# industrialSensorModule.net
KiCad netlist of a schematic drawn in EAGLE
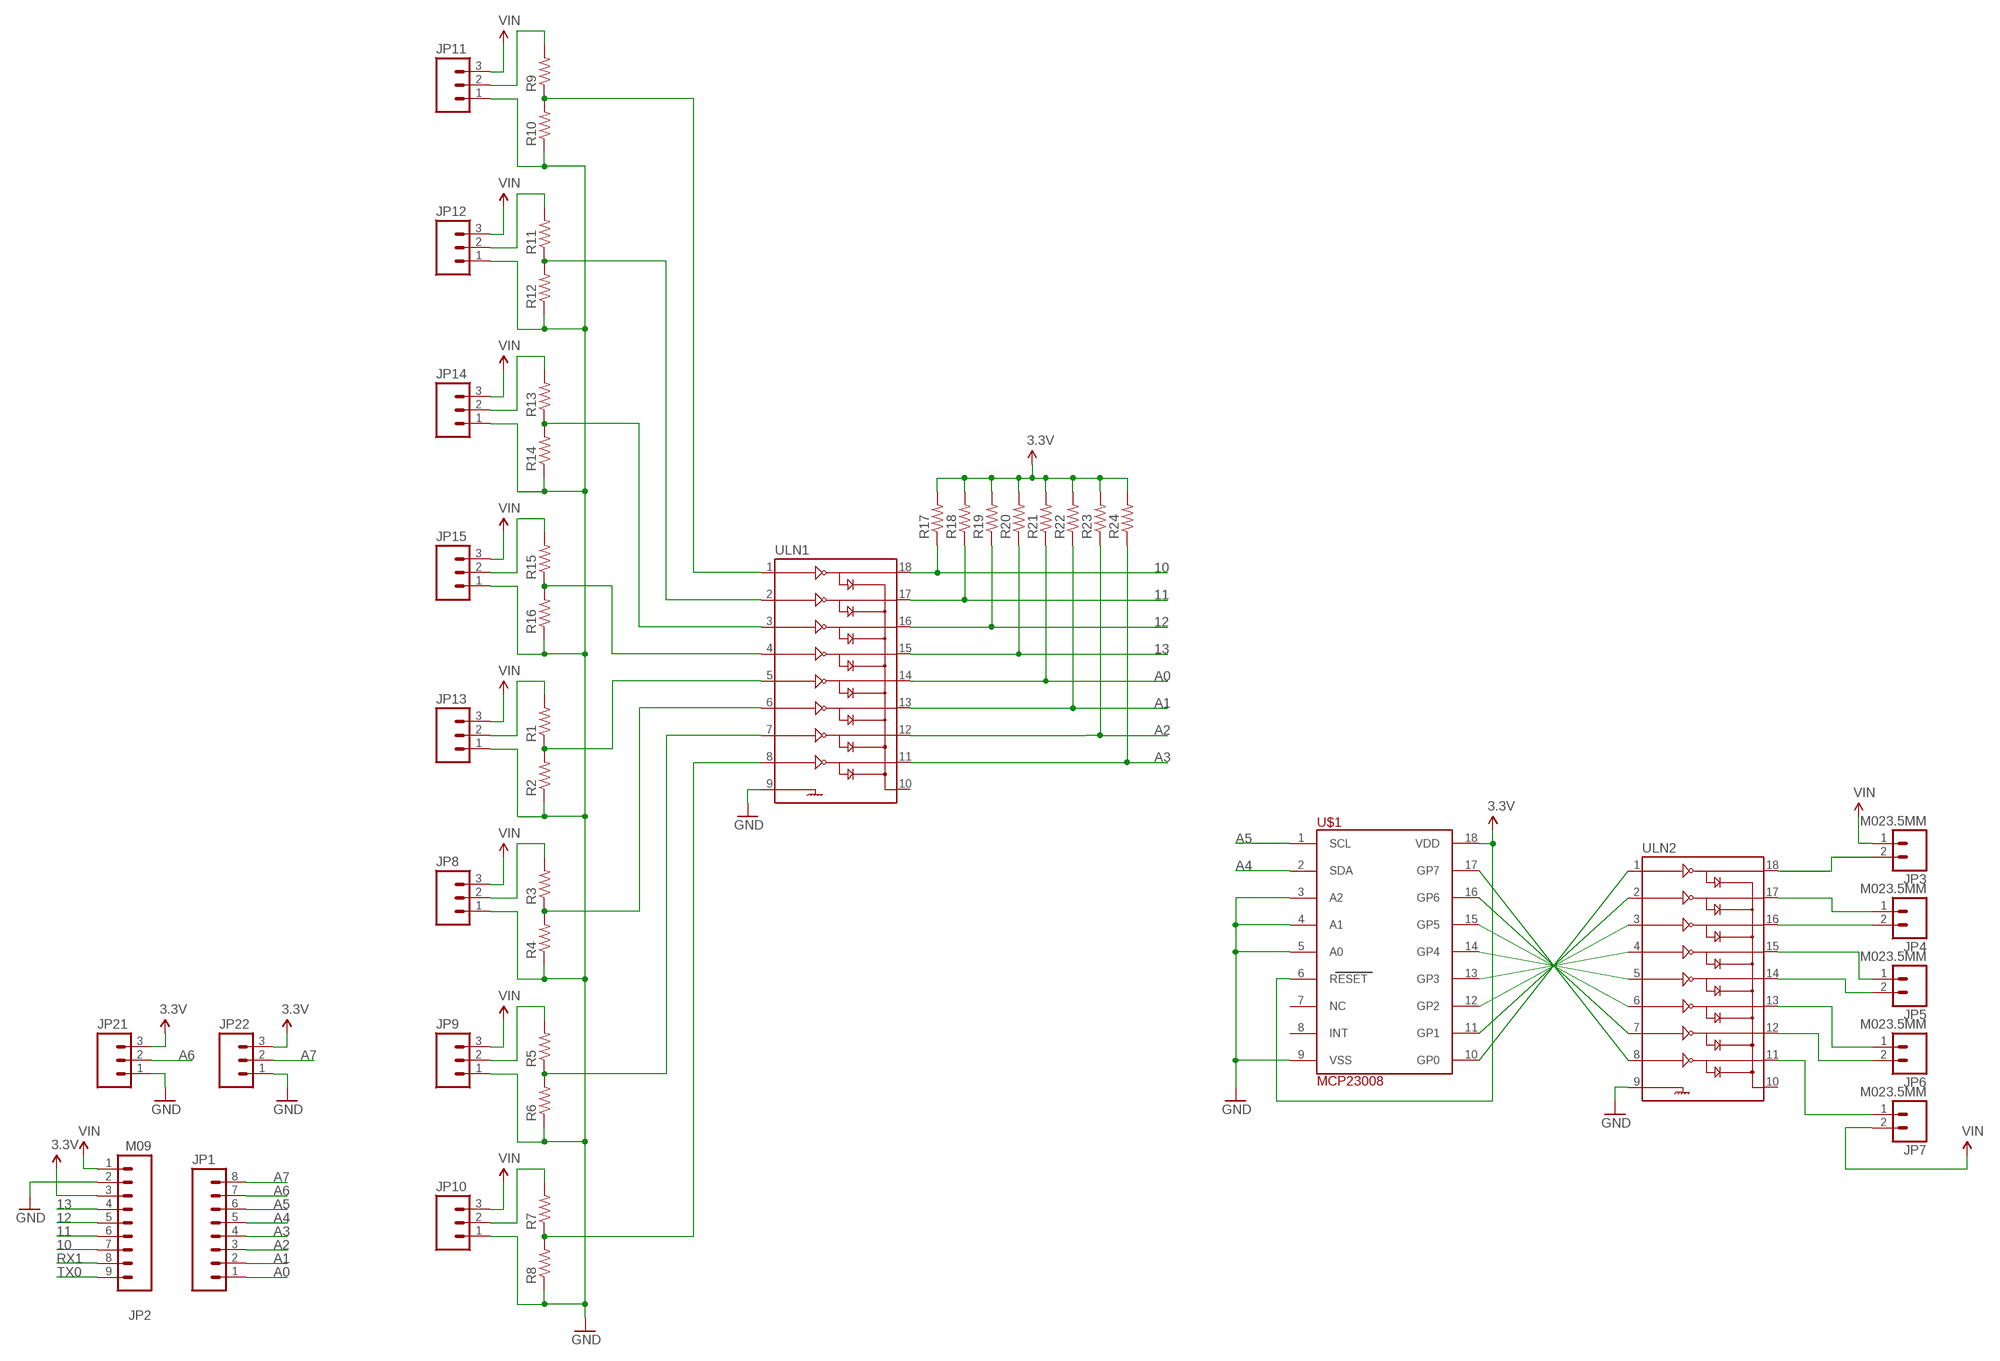
[diagram p0: schematic, sheet 1]

(export (version "E")
  (design (tool "Eeschema 10.0.6"))
  (components
    (comp (ref "JP1")
      (value "M081X08")
      (footprint "eagle-import:1X08")
      (libsource (lib "eagle-import") (part "M081X08"))
    )
    (comp (ref "JP2")
      (value "M09")
      (footprint "eagle-import:1X09")
      (libsource (lib "eagle-import") (part "M09"))
    )
    (comp (ref "JP3")
      (value "M023.5MM")
      (footprint "eagle-import:SCREWTERMINAL-3.5MM-2")
      (libsource (lib "eagle-import") (part "M023.5MM"))
    )
    (comp (ref "JP4")
      (value "M023.5MM")
      (footprint "eagle-import:SCREWTERMINAL-3.5MM-2")
      (libsource (lib "eagle-import") (part "M023.5MM"))
    )
    (comp (ref "JP5")
      (value "M023.5MM")
      (footprint "eagle-import:SCREWTERMINAL-3.5MM-2")
      (libsource (lib "eagle-import") (part "M023.5MM"))
    )
    (comp (ref "JP6")
      (value "M023.5MM")
      (footprint "eagle-import:SCREWTERMINAL-3.5MM-2")
      (libsource (lib "eagle-import") (part "M023.5MM"))
    )
    (comp (ref "JP7")
      (value "M023.5MM")
      (footprint "eagle-import:SCREWTERMINAL-3.5MM-2")
      (libsource (lib "eagle-import") (part "M023.5MM"))
    )
    (comp (ref "JP8")
      (value "M03SCREW")
      (footprint "eagle-import:SCREWTERMINAL-3.5MM-3")
      (libsource (lib "eagle-import") (part "M03SCREW"))
    )
    (comp (ref "JP9")
      (value "M03SCREW")
      (footprint "eagle-import:SCREWTERMINAL-3.5MM-3")
      (libsource (lib "eagle-import") (part "M03SCREW"))
    )
    (comp (ref "JP10")
      (value "M03SCREW")
      (footprint "eagle-import:SCREWTERMINAL-3.5MM-3")
      (libsource (lib "eagle-import") (part "M03SCREW"))
    )
    (comp (ref "JP11")
      (value "M03SCREW")
      (footprint "eagle-import:SCREWTERMINAL-3.5MM-3")
      (libsource (lib "eagle-import") (part "M03SCREW"))
    )
    (comp (ref "JP12")
      (value "M03SCREW")
      (footprint "eagle-import:SCREWTERMINAL-3.5MM-3")
      (libsource (lib "eagle-import") (part "M03SCREW"))
    )
    (comp (ref "JP13")
      (value "M03SCREW")
      (footprint "eagle-import:SCREWTERMINAL-3.5MM-3")
      (libsource (lib "eagle-import") (part "M03SCREW"))
    )
    (comp (ref "JP14")
      (value "M03SCREW")
      (footprint "eagle-import:SCREWTERMINAL-3.5MM-3")
      (libsource (lib "eagle-import") (part "M03SCREW"))
    )
    (comp (ref "JP15")
      (value "M03SCREW")
      (footprint "eagle-import:SCREWTERMINAL-3.5MM-3")
      (libsource (lib "eagle-import") (part "M03SCREW"))
    )
    (comp (ref "JP21")
      (value "M03SCREW")
      (footprint "eagle-import:SCREWTERMINAL-3.5MM-3")
      (libsource (lib "eagle-import") (part "M03SCREW"))
    )
    (comp (ref "JP22")
      (value "M03SCREW")
      (footprint "eagle-import:SCREWTERMINAL-3.5MM-3")
      (libsource (lib "eagle-import") (part "M03SCREW"))
    )
    (comp (ref "R1")
      (value "RESISTOR1206")
      (footprint "eagle-import:1206")
      (libsource (lib "eagle-import") (part "RESISTOR1206"))
    )
    (comp (ref "R2")
      (value "RESISTOR1206")
      (footprint "eagle-import:1206")
      (libsource (lib "eagle-import") (part "RESISTOR1206"))
    )
    (comp (ref "R3")
      (value "RESISTOR1206")
      (footprint "eagle-import:1206")
      (libsource (lib "eagle-import") (part "RESISTOR1206"))
    )
    (comp (ref "R4")
      (value "RESISTOR1206")
      (footprint "eagle-import:1206")
      (libsource (lib "eagle-import") (part "RESISTOR1206"))
    )
    (comp (ref "R5")
      (value "RESISTOR1206")
      (footprint "eagle-import:1206")
      (libsource (lib "eagle-import") (part "RESISTOR1206"))
    )
    (comp (ref "R6")
      (value "RESISTOR1206")
      (footprint "eagle-import:1206")
      (libsource (lib "eagle-import") (part "RESISTOR1206"))
    )
    (comp (ref "R7")
      (value "RESISTOR1206")
      (footprint "eagle-import:1206")
      (libsource (lib "eagle-import") (part "RESISTOR1206"))
    )
    (comp (ref "R8")
      (value "RESISTOR1206")
      (footprint "eagle-import:1206")
      (libsource (lib "eagle-import") (part "RESISTOR1206"))
    )
    (comp (ref "R9")
      (value "RESISTOR1206")
      (footprint "eagle-import:1206")
      (libsource (lib "eagle-import") (part "RESISTOR1206"))
    )
    (comp (ref "R10")
      (value "RESISTOR1206")
      (footprint "eagle-import:1206")
      (libsource (lib "eagle-import") (part "RESISTOR1206"))
    )
    (comp (ref "R11")
      (value "RESISTOR1206")
      (footprint "eagle-import:1206")
      (libsource (lib "eagle-import") (part "RESISTOR1206"))
    )
    (comp (ref "R12")
      (value "RESISTOR1206")
      (footprint "eagle-import:1206")
      (libsource (lib "eagle-import") (part "RESISTOR1206"))
    )
    (comp (ref "R13")
      (value "RESISTOR1206")
      (footprint "eagle-import:1206")
      (libsource (lib "eagle-import") (part "RESISTOR1206"))
    )
    (comp (ref "R14")
      (value "RESISTOR1206")
      (footprint "eagle-import:1206")
      (libsource (lib "eagle-import") (part "RESISTOR1206"))
    )
    (comp (ref "R15")
      (value "RESISTOR1206")
      (footprint "eagle-import:1206")
      (libsource (lib "eagle-import") (part "RESISTOR1206"))
    )
    (comp (ref "R16")
      (value "RESISTOR1206")
      (footprint "eagle-import:1206")
      (libsource (lib "eagle-import") (part "RESISTOR1206"))
    )
    (comp (ref "R17")
      (value "RESISTOR1206")
      (footprint "eagle-import:1206")
      (libsource (lib "eagle-import") (part "RESISTOR1206"))
    )
    (comp (ref "R18")
      (value "RESISTOR1206")
      (footprint "eagle-import:1206")
      (libsource (lib "eagle-import") (part "RESISTOR1206"))
    )
    (comp (ref "R19")
      (value "RESISTOR1206")
      (footprint "eagle-import:1206")
      (libsource (lib "eagle-import") (part "RESISTOR1206"))
    )
    (comp (ref "R20")
      (value "RESISTOR1206")
      (footprint "eagle-import:1206")
      (libsource (lib "eagle-import") (part "RESISTOR1206"))
    )
    (comp (ref "R21")
      (value "RESISTOR1206")
      (footprint "eagle-import:1206")
      (libsource (lib "eagle-import") (part "RESISTOR1206"))
    )
    (comp (ref "R22")
      (value "RESISTOR1206")
      (footprint "eagle-import:1206")
      (libsource (lib "eagle-import") (part "RESISTOR1206"))
    )
    (comp (ref "R23")
      (value "RESISTOR1206")
      (footprint "eagle-import:1206")
      (libsource (lib "eagle-import") (part "RESISTOR1206"))
    )
    (comp (ref "R24")
      (value "RESISTOR1206")
      (footprint "eagle-import:1206")
      (libsource (lib "eagle-import") (part "RESISTOR1206"))
    )
    (comp (ref "U$1")
      (value "MCP23008")
      (footprint "eagle-import:SOICW-18")
      (libsource (lib "eagle-import") (part "MCP23008"))
    )
    (comp (ref "ULN1")
      (value "ULN2803SOICW")
      (footprint "eagle-import:SO18L")
      (libsource (lib "eagle-import") (part "ULN2803SOICW"))
    )
    (comp (ref "ULN2")
      (value "ULN2803SOICW")
      (footprint "eagle-import:SO18L")
      (libsource (lib "eagle-import") (part "ULN2803SOICW"))
    )
  )
  (nets
    (net (code "1") (name "/10") (class "Default")
      (node (ref "JP2") (pin "7") (pinfunction "7_7") (pintype "passive"))
      (node (ref "R17") (pin "1") (pinfunction "1_1") (pintype "passive"))
      (node (ref "ULN1") (pin "18") (pinfunction "18_18") (pintype "bidirectional"))
    )
    (net (code "2") (name "/11") (class "Default")
      (node (ref "JP2") (pin "6") (pinfunction "6_6") (pintype "passive"))
      (node (ref "R18") (pin "1") (pinfunction "1_1") (pintype "passive"))
      (node (ref "ULN1") (pin "17") (pinfunction "17_17") (pintype "bidirectional"))
    )
    (net (code "3") (name "/12") (class "Default")
      (node (ref "JP2") (pin "5") (pinfunction "5_5") (pintype "passive"))
      (node (ref "R19") (pin "1") (pinfunction "1_1") (pintype "passive"))
      (node (ref "ULN1") (pin "16") (pinfunction "16_16") (pintype "bidirectional"))
    )
    (net (code "4") (name "/13") (class "Default")
      (node (ref "JP2") (pin "4") (pinfunction "4_4") (pintype "passive"))
      (node (ref "R20") (pin "1") (pinfunction "1_1") (pintype "passive"))
      (node (ref "ULN1") (pin "15") (pinfunction "15_15") (pintype "bidirectional"))
    )
    (net (code "5") (name "/A0") (class "Default")
      (node (ref "JP1") (pin "1") (pinfunction "1_1") (pintype "passive"))
      (node (ref "R21") (pin "1") (pinfunction "1_1") (pintype "passive"))
      (node (ref "ULN1") (pin "14") (pinfunction "14_14") (pintype "bidirectional"))
    )
    (net (code "6") (name "/A1") (class "Default")
      (node (ref "JP1") (pin "2") (pinfunction "2_2") (pintype "passive"))
      (node (ref "R22") (pin "1") (pinfunction "1_1") (pintype "passive"))
      (node (ref "ULN1") (pin "13") (pinfunction "13_13") (pintype "bidirectional"))
    )
    (net (code "7") (name "/A2") (class "Default")
      (node (ref "JP1") (pin "3") (pinfunction "3_3") (pintype "passive"))
      (node (ref "R23") (pin "1") (pinfunction "1_1") (pintype "passive"))
      (node (ref "ULN1") (pin "12") (pinfunction "12_12") (pintype "bidirectional"))
    )
    (net (code "8") (name "/A3") (class "Default")
      (node (ref "JP1") (pin "4") (pinfunction "4_4") (pintype "passive"))
      (node (ref "R24") (pin "1") (pinfunction "1_1") (pintype "passive"))
      (node (ref "ULN1") (pin "11") (pinfunction "11_11") (pintype "bidirectional"))
    )
    (net (code "9") (name "/A4") (class "Default")
      (node (ref "JP1") (pin "5") (pinfunction "5_5") (pintype "passive"))
      (node (ref "U$1") (pin "2") (pinfunction "SDA_2") (pintype "bidirectional"))
    )
    (net (code "10") (name "/A5") (class "Default")
      (node (ref "JP1") (pin "6") (pinfunction "6_6") (pintype "passive"))
      (node (ref "U$1") (pin "1") (pinfunction "SCL_1") (pintype "bidirectional"))
    )
    (net (code "11") (name "/A6") (class "Default")
      (node (ref "JP1") (pin "7") (pinfunction "7_7") (pintype "passive"))
      (node (ref "JP21") (pin "2") (pinfunction "2_2") (pintype "passive"))
    )
    (net (code "12") (name "/A7") (class "Default")
      (node (ref "JP1") (pin "8") (pinfunction "8_8") (pintype "passive"))
      (node (ref "JP22") (pin "2") (pinfunction "2_2") (pintype "passive"))
    )
    (net (code "13") (name "/RX1") (class "Default")
      (node (ref "JP2") (pin "8") (pinfunction "8_8") (pintype "passive"))
    )
    (net (code "14") (name "/TX0") (class "Default")
      (node (ref "JP2") (pin "9") (pinfunction "9_9") (pintype "passive"))
    )
    (net (code "15") (name "3.3V") (class "Default")
      (node (ref "JP2") (pin "3") (pinfunction "3_3") (pintype "passive"))
      (node (ref "JP21") (pin "3") (pinfunction "3_3") (pintype "passive"))
      (node (ref "JP22") (pin "3") (pinfunction "3_3") (pintype "passive"))
      (node (ref "R17") (pin "2") (pinfunction "2_2") (pintype "passive"))
      (node (ref "R18") (pin "2") (pinfunction "2_2") (pintype "passive"))
      (node (ref "R19") (pin "2") (pinfunction "2_2") (pintype "passive"))
      (node (ref "R20") (pin "2") (pinfunction "2_2") (pintype "passive"))
      (node (ref "R21") (pin "2") (pinfunction "2_2") (pintype "passive"))
      (node (ref "R22") (pin "2") (pinfunction "2_2") (pintype "passive"))
      (node (ref "R23") (pin "2") (pinfunction "2_2") (pintype "passive"))
      (node (ref "R24") (pin "2") (pinfunction "2_2") (pintype "passive"))
      (node (ref "U$1") (pin "18") (pinfunction "VDD_18") (pintype "power_in"))
      (node (ref "U$1") (pin "6") (pinfunction "RESET_6") (pintype "input"))
    )
    (net (code "16") (name "GND") (class "Default")
      (node (ref "JP10") (pin "1") (pinfunction "1_1") (pintype "passive"))
      (node (ref "JP11") (pin "1") (pinfunction "1_1") (pintype "passive"))
      (node (ref "JP12") (pin "1") (pinfunction "1_1") (pintype "passive"))
      (node (ref "JP13") (pin "1") (pinfunction "1_1") (pintype "passive"))
      (node (ref "JP14") (pin "1") (pinfunction "1_1") (pintype "passive"))
      (node (ref "JP15") (pin "1") (pinfunction "1_1") (pintype "passive"))
      (node (ref "JP2") (pin "2") (pinfunction "2_2") (pintype "passive"))
      (node (ref "JP21") (pin "1") (pinfunction "1_1") (pintype "passive"))
      (node (ref "JP22") (pin "1") (pinfunction "1_1") (pintype "passive"))
      (node (ref "JP8") (pin "1") (pinfunction "1_1") (pintype "passive"))
      (node (ref "JP9") (pin "1") (pinfunction "1_1") (pintype "passive"))
      (node (ref "R10") (pin "1") (pinfunction "1_1") (pintype "passive"))
      (node (ref "R12") (pin "1") (pinfunction "1_1") (pintype "passive"))
      (node (ref "R14") (pin "1") (pinfunction "1_1") (pintype "passive"))
      (node (ref "R16") (pin "1") (pinfunction "1_1") (pintype "passive"))
      (node (ref "R2") (pin "1") (pinfunction "1_1") (pintype "passive"))
      (node (ref "R4") (pin "1") (pinfunction "1_1") (pintype "passive"))
      (node (ref "R6") (pin "1") (pinfunction "1_1") (pintype "passive"))
      (node (ref "R8") (pin "1") (pinfunction "1_1") (pintype "passive"))
      (node (ref "U$1") (pin "3") (pinfunction "A2_3") (pintype "input"))
      (node (ref "U$1") (pin "4") (pinfunction "A1_4") (pintype "input"))
      (node (ref "U$1") (pin "5") (pinfunction "A0_5") (pintype "input"))
      (node (ref "U$1") (pin "9") (pinfunction "VSS_9") (pintype "power_in"))
      (node (ref "ULN1") (pin "9") (pinfunction "9_9") (pintype "bidirectional"))
      (node (ref "ULN2") (pin "9") (pinfunction "9_9") (pintype "bidirectional"))
    )
    (net (code "17") (name "Net-(JP3-Pad2)") (class "Default")
      (node (ref "JP3") (pin "2") (pinfunction "2_2") (pintype "passive"))
      (node (ref "ULN2") (pin "18") (pinfunction "18_18") (pintype "bidirectional"))
    )
    (net (code "18") (name "Net-(JP4-Pad1)") (class "Default")
      (node (ref "JP4") (pin "1") (pinfunction "1_1") (pintype "passive"))
      (node (ref "ULN2") (pin "17") (pinfunction "17_17") (pintype "bidirectional"))
    )
    (net (code "19") (name "Net-(JP4-Pad2)") (class "Default")
      (node (ref "JP4") (pin "2") (pinfunction "2_2") (pintype "passive"))
      (node (ref "ULN2") (pin "16") (pinfunction "16_16") (pintype "bidirectional"))
    )
    (net (code "20") (name "Net-(JP5-Pad1)") (class "Default")
      (node (ref "JP5") (pin "1") (pinfunction "1_1") (pintype "passive"))
      (node (ref "ULN2") (pin "15") (pinfunction "15_15") (pintype "bidirectional"))
    )
    (net (code "21") (name "Net-(JP5-Pad2)") (class "Default")
      (node (ref "JP5") (pin "2") (pinfunction "2_2") (pintype "passive"))
      (node (ref "ULN2") (pin "14") (pinfunction "14_14") (pintype "bidirectional"))
    )
    (net (code "22") (name "Net-(JP6-Pad1)") (class "Default")
      (node (ref "JP6") (pin "1") (pinfunction "1_1") (pintype "passive"))
      (node (ref "ULN2") (pin "13") (pinfunction "13_13") (pintype "bidirectional"))
    )
    (net (code "23") (name "Net-(JP6-Pad2)") (class "Default")
      (node (ref "JP6") (pin "2") (pinfunction "2_2") (pintype "passive"))
      (node (ref "ULN2") (pin "12") (pinfunction "12_12") (pintype "bidirectional"))
    )
    (net (code "24") (name "Net-(JP7-Pad1)") (class "Default")
      (node (ref "JP7") (pin "1") (pinfunction "1_1") (pintype "passive"))
      (node (ref "ULN2") (pin "11") (pinfunction "11_11") (pintype "bidirectional"))
    )
    (net (code "25") (name "Net-(JP8-Pad2)") (class "Default")
      (node (ref "JP8") (pin "2") (pinfunction "2_2") (pintype "passive"))
      (node (ref "R3") (pin "2") (pinfunction "2_2") (pintype "passive"))
    )
    (net (code "26") (name "Net-(JP9-Pad2)") (class "Default")
      (node (ref "JP9") (pin "2") (pinfunction "2_2") (pintype "passive"))
      (node (ref "R5") (pin "2") (pinfunction "2_2") (pintype "passive"))
    )
    (net (code "27") (name "Net-(JP10-Pad2)") (class "Default")
      (node (ref "JP10") (pin "2") (pinfunction "2_2") (pintype "passive"))
      (node (ref "R7") (pin "2") (pinfunction "2_2") (pintype "passive"))
    )
    (net (code "28") (name "Net-(JP11-Pad2)") (class "Default")
      (node (ref "JP11") (pin "2") (pinfunction "2_2") (pintype "passive"))
      (node (ref "R9") (pin "2") (pinfunction "2_2") (pintype "passive"))
    )
    (net (code "29") (name "Net-(JP12-Pad2)") (class "Default")
      (node (ref "JP12") (pin "2") (pinfunction "2_2") (pintype "passive"))
      (node (ref "R11") (pin "2") (pinfunction "2_2") (pintype "passive"))
    )
    (net (code "30") (name "Net-(JP13-Pad2)") (class "Default")
      (node (ref "JP13") (pin "2") (pinfunction "2_2") (pintype "passive"))
      (node (ref "R1") (pin "2") (pinfunction "2_2") (pintype "passive"))
    )
    (net (code "31") (name "Net-(JP14-Pad2)") (class "Default")
      (node (ref "JP14") (pin "2") (pinfunction "2_2") (pintype "passive"))
      (node (ref "R13") (pin "2") (pinfunction "2_2") (pintype "passive"))
    )
    (net (code "32") (name "Net-(JP15-Pad2)") (class "Default")
      (node (ref "JP15") (pin "2") (pinfunction "2_2") (pintype "passive"))
      (node (ref "R15") (pin "2") (pinfunction "2_2") (pintype "passive"))
    )
    (net (code "33") (name "Net-(R1-Pad1)") (class "Default")
      (node (ref "R1") (pin "1") (pinfunction "1_1") (pintype "passive"))
      (node (ref "R2") (pin "2") (pinfunction "2_2") (pintype "passive"))
      (node (ref "ULN1") (pin "5") (pinfunction "5_5") (pintype "bidirectional"))
    )
    (net (code "34") (name "Net-(R3-Pad1)") (class "Default")
      (node (ref "R3") (pin "1") (pinfunction "1_1") (pintype "passive"))
      (node (ref "R4") (pin "2") (pinfunction "2_2") (pintype "passive"))
      (node (ref "ULN1") (pin "6") (pinfunction "6_6") (pintype "bidirectional"))
    )
    (net (code "35") (name "Net-(R5-Pad1)") (class "Default")
      (node (ref "R5") (pin "1") (pinfunction "1_1") (pintype "passive"))
      (node (ref "R6") (pin "2") (pinfunction "2_2") (pintype "passive"))
      (node (ref "ULN1") (pin "7") (pinfunction "7_7") (pintype "bidirectional"))
    )
    (net (code "36") (name "Net-(R7-Pad1)") (class "Default")
      (node (ref "R7") (pin "1") (pinfunction "1_1") (pintype "passive"))
      (node (ref "R8") (pin "2") (pinfunction "2_2") (pintype "passive"))
      (node (ref "ULN1") (pin "8") (pinfunction "8_8") (pintype "bidirectional"))
    )
    (net (code "37") (name "Net-(R10-Pad2)") (class "Default")
      (node (ref "R10") (pin "2") (pinfunction "2_2") (pintype "passive"))
      (node (ref "R9") (pin "1") (pinfunction "1_1") (pintype "passive"))
      (node (ref "ULN1") (pin "1") (pinfunction "1_1") (pintype "bidirectional"))
    )
    (net (code "38") (name "Net-(R11-Pad1)") (class "Default")
      (node (ref "R11") (pin "1") (pinfunction "1_1") (pintype "passive"))
      (node (ref "R12") (pin "2") (pinfunction "2_2") (pintype "passive"))
      (node (ref "ULN1") (pin "2") (pinfunction "2_2") (pintype "bidirectional"))
    )
    (net (code "39") (name "Net-(R13-Pad1)") (class "Default")
      (node (ref "R13") (pin "1") (pinfunction "1_1") (pintype "passive"))
      (node (ref "R14") (pin "2") (pinfunction "2_2") (pintype "passive"))
      (node (ref "ULN1") (pin "3") (pinfunction "3_3") (pintype "bidirectional"))
    )
    (net (code "40") (name "Net-(R15-Pad1)") (class "Default")
      (node (ref "R15") (pin "1") (pinfunction "1_1") (pintype "passive"))
      (node (ref "R16") (pin "2") (pinfunction "2_2") (pintype "passive"))
      (node (ref "ULN1") (pin "4") (pinfunction "4_4") (pintype "bidirectional"))
    )
    (net (code "41") (name "Net-(U$1-GP0)") (class "Default")
      (node (ref "U$1") (pin "10") (pinfunction "GP0_10") (pintype "bidirectional"))
      (node (ref "ULN2") (pin "1") (pinfunction "1_1") (pintype "bidirectional"))
    )
    (net (code "42") (name "Net-(U$1-GP1)") (class "Default")
      (node (ref "U$1") (pin "11") (pinfunction "GP1_11") (pintype "bidirectional"))
      (node (ref "ULN2") (pin "2") (pinfunction "2_2") (pintype "bidirectional"))
    )
    (net (code "43") (name "Net-(U$1-GP2)") (class "Default")
      (node (ref "U$1") (pin "12") (pinfunction "GP2_12") (pintype "bidirectional"))
      (node (ref "ULN2") (pin "3") (pinfunction "3_3") (pintype "bidirectional"))
    )
    (net (code "44") (name "Net-(U$1-GP3)") (class "Default")
      (node (ref "U$1") (pin "13") (pinfunction "GP3_13") (pintype "bidirectional"))
      (node (ref "ULN2") (pin "4") (pinfunction "4_4") (pintype "bidirectional"))
    )
    (net (code "45") (name "Net-(U$1-GP4)") (class "Default")
      (node (ref "U$1") (pin "14") (pinfunction "GP4_14") (pintype "bidirectional"))
      (node (ref "ULN2") (pin "5") (pinfunction "5_5") (pintype "bidirectional"))
    )
    (net (code "46") (name "Net-(U$1-GP5)") (class "Default")
      (node (ref "U$1") (pin "15") (pinfunction "GP5_15") (pintype "bidirectional"))
      (node (ref "ULN2") (pin "6") (pinfunction "6_6") (pintype "bidirectional"))
    )
    (net (code "47") (name "Net-(U$1-GP6)") (class "Default")
      (node (ref "U$1") (pin "16") (pinfunction "GP6_16") (pintype "bidirectional"))
      (node (ref "ULN2") (pin "7") (pinfunction "7_7") (pintype "bidirectional"))
    )
    (net (code "48") (name "Net-(U$1-GP7)") (class "Default")
      (node (ref "U$1") (pin "17") (pinfunction "GP7_17") (pintype "bidirectional"))
      (node (ref "ULN2") (pin "8") (pinfunction "8_8") (pintype "bidirectional"))
    )
    (net (code "49") (name "VIN") (class "Default")
      (node (ref "JP10") (pin "3") (pinfunction "3_3") (pintype "passive"))
      (node (ref "JP11") (pin "3") (pinfunction "3_3") (pintype "passive"))
      (node (ref "JP12") (pin "3") (pinfunction "3_3") (pintype "passive"))
      (node (ref "JP13") (pin "3") (pinfunction "3_3") (pintype "passive"))
      (node (ref "JP14") (pin "3") (pinfunction "3_3") (pintype "passive"))
      (node (ref "JP15") (pin "3") (pinfunction "3_3") (pintype "passive"))
      (node (ref "JP2") (pin "1") (pinfunction "1_1") (pintype "passive"))
      (node (ref "JP3") (pin "1") (pinfunction "1_1") (pintype "passive"))
      (node (ref "JP7") (pin "2") (pinfunction "2_2") (pintype "passive"))
      (node (ref "JP8") (pin "3") (pinfunction "3_3") (pintype "passive"))
      (node (ref "JP9") (pin "3") (pinfunction "3_3") (pintype "passive"))
    )
    (net (code "50") (name "unconnected-(U$1-INT-Pad8)") (class "Default")
      (node (ref "U$1") (pin "8") (pinfunction "INT_8") (pintype "input"))
    )
    (net (code "51") (name "unconnected-(U$1-NC-Pad7)") (class "Default")
      (node (ref "U$1") (pin "7") (pinfunction "NC_7") (pintype "no_connect"))
    )
    (net (code "52") (name "unconnected-(ULN1-Pad10)") (class "Default")
      (node (ref "ULN1") (pin "10") (pinfunction "10_10") (pintype "bidirectional"))
    )
    (net (code "53") (name "unconnected-(ULN2-Pad10)") (class "Default")
      (node (ref "ULN2") (pin "10") (pinfunction "10_10") (pintype "bidirectional"))
    )
  )
)
